# ABoatMon.net
KiCad netlist of a schematic drawn in EAGLE
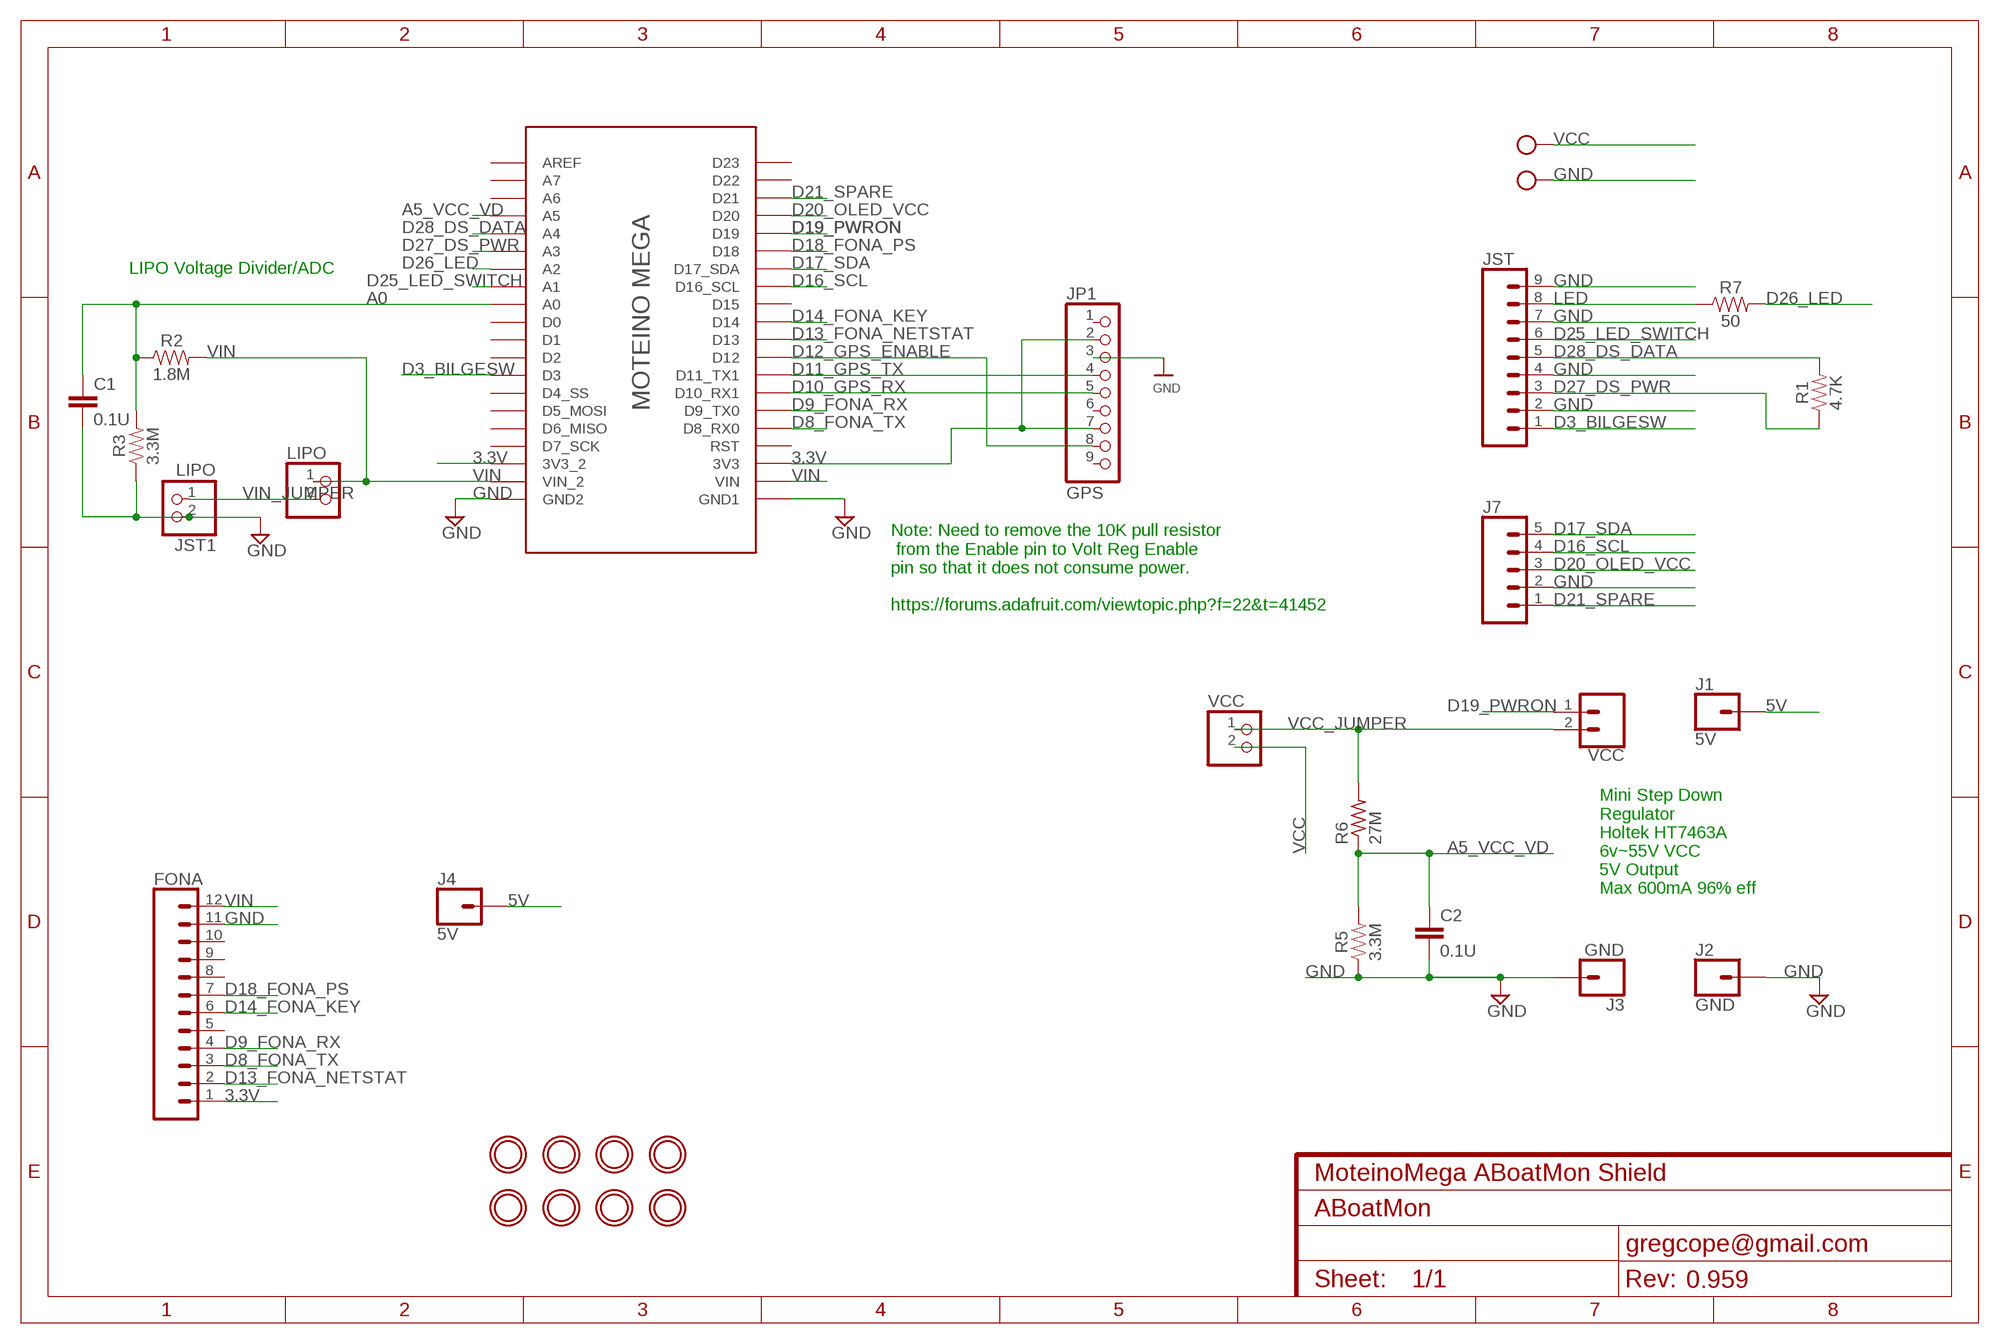
[diagram p0: schematic, sheet 1]

(export (version "E")
  (design (tool "Eeschema 10.0.6"))
  (components
    (comp (ref "C1")
      (value "0.1U")
      (footprint "eagle-import:CAP-PTH-SMALL-KIT")
      (libsource (lib "eagle-import") (part "0.1UF-KIT-EZ-50V-20%"))
    )
    (comp (ref "C2")
      (value "0.1U")
      (footprint "eagle-import:CAP-PTH-SMALL-KIT")
      (libsource (lib "eagle-import") (part "0.1UF-KIT-EZ-50V-20%"))
    )
    (comp (ref "ENABLE")
      (value "VCC")
      (footprint "eagle-import:1X02")
      (libsource (lib "eagle-import") (part "CONN_02"))
    )
    (comp (ref "FONA")
      (value "CONN_12")
      (footprint "eagle-import:1X12")
      (libsource (lib "eagle-import") (part "CONN_12"))
    )
    (comp (ref "GND")
      (value "MOUNTINGHOLE2.5")
      (footprint "eagle-import:MOUNTINGHOLE_2.5_PLATED")
      (libsource (lib "eagle-import") (part "MOUNTINGHOLE2.5"))
    )
    (comp (ref "J1")
      (value "5V")
      (footprint "eagle-import:1X01")
      (libsource (lib "eagle-import") (part "CONN_01"))
    )
    (comp (ref "J2")
      (value "GND")
      (footprint "eagle-import:1X01")
      (libsource (lib "eagle-import") (part "CONN_01"))
    )
    (comp (ref "J3")
      (value "GND")
      (footprint "eagle-import:1X01")
      (libsource (lib "eagle-import") (part "CONN_01"))
    )
    (comp (ref "J4")
      (value "5V")
      (footprint "eagle-import:1X01")
      (libsource (lib "eagle-import") (part "CONN_01"))
    )
    (comp (ref "J7")
      (value "CONN_05NO_SILK")
      (footprint "eagle-import:1X05_NO_SILK")
      (libsource (lib "eagle-import") (part "CONN_05NO_SILK"))
    )
    (comp (ref "JP1")
      (value "GPS")
      (footprint "eagle-import:1X09_ROUND_70")
      (libsource (lib "eagle-import") (part "HEADER-1X970MIL"))
    )
    (comp (ref "JST")
      (value "CONN_09")
      (footprint "eagle-import:1X09")
      (libsource (lib "eagle-import") (part "CONN_09"))
    )
    (comp (ref "JST1")
      (value "LIPO")
      (footprint "eagle-import:JST-PH-2-THM")
      (libsource (lib "eagle-import") (part "JST_2PIN-THM"))
    )
    (comp (ref "LIPO")
      (value "HEADER-1X2ROUND")
      (footprint "eagle-import:1X02_ROUND")
      (libsource (lib "eagle-import") (part "HEADER-1X2ROUND"))
    )
    (comp (ref "MOTEINO_MEGA")
      (value "HEADERS")
      (footprint "eagle-import:MOTEINO_MEGA_SIMPLE")
      (libsource (lib "eagle-import") (part "MOTEINO_MEGA_SIMPLE"))
    )
    (comp (ref "R1")
      (value "4.7K")
      (footprint "eagle-import:AXIAL-0.3")
      (libsource (lib "eagle-import") (part "1KOHM-HORIZ-1/4W-1%"))
    )
    (comp (ref "R2")
      (value "1.8M")
      (footprint "eagle-import:AXIAL-0.3")
      (libsource (lib "eagle-import") (part "1KOHM-HORIZ-1/4W-1%"))
    )
    (comp (ref "R3")
      (value "3.3M")
      (footprint "eagle-import:AXIAL-0.3")
      (libsource (lib "eagle-import") (part "1KOHM-HORIZ-1/4W-1%"))
    )
    (comp (ref "R5")
      (value "3.3M")
      (footprint "eagle-import:AXIAL-0.3")
      (libsource (lib "eagle-import") (part "1KOHM-HORIZ-1/4W-1%"))
    )
    (comp (ref "R6")
      (value "27M")
      (footprint "eagle-import:0309_12")
      (libsource (lib "eagle-import") (part "R-US_0309/12"))
    )
    (comp (ref "R7")
      (value "50")
      (footprint "eagle-import:AXIAL-0.3")
      (libsource (lib "eagle-import") (part "1KOHM-HORIZ-1/4W-1%"))
    )
    (comp (ref "U$1")
      (value "MOUNTINGHOLE2.5")
      (footprint "eagle-import:MOUNTINGHOLE_2.5_PLATED")
      (libsource (lib "eagle-import") (part "MOUNTINGHOLE2.5"))
    )
    (comp (ref "U$2")
      (value "MOUNTINGHOLE2.5")
      (footprint "eagle-import:MOUNTINGHOLE_2.5_PLATED")
      (libsource (lib "eagle-import") (part "MOUNTINGHOLE2.5"))
    )
    (comp (ref "U$3")
      (value "MOUNTINGHOLE2.5")
      (footprint "eagle-import:MOUNTINGHOLE_2.5_PLATED")
      (libsource (lib "eagle-import") (part "MOUNTINGHOLE2.5"))
    )
    (comp (ref "U$4")
      (value "MOUNTINGHOLE2.5")
      (footprint "eagle-import:MOUNTINGHOLE_2.5_PLATED")
      (libsource (lib "eagle-import") (part "MOUNTINGHOLE2.5"))
    )
    (comp (ref "U$5")
      (value "MOUNTINGHOLE2.5")
      (footprint "eagle-import:MOUNTINGHOLE_2.5_PLATED")
      (libsource (lib "eagle-import") (part "MOUNTINGHOLE2.5"))
    )
    (comp (ref "U$7")
      (value "MOUNTINGHOLE2.5")
      (footprint "eagle-import:MOUNTINGHOLE_2.5_PLATED")
      (libsource (lib "eagle-import") (part "MOUNTINGHOLE2.5"))
    )
    (comp (ref "U$8")
      (value "MOUNTINGHOLE2.5")
      (footprint "eagle-import:MOUNTINGHOLE_2.5_PLATED")
      (libsource (lib "eagle-import") (part "MOUNTINGHOLE2.5"))
    )
    (comp (ref "VCC")
      (value "HEADER-1X2ROUND")
      (footprint "eagle-import:1X02_ROUND")
      (libsource (lib "eagle-import") (part "HEADER-1X2ROUND"))
    )
    (comp (ref "X1")
      (value "MKDSN1,5/2-5,08")
      (footprint "eagle-import:MKDSN1,5_2-5,08")
      (libsource (lib "eagle-import") (part "MKDSN1,5/2-5,08"))
    )
  )
  (nets
    (net (code "1") (name "/3.3V") (class "Default")
      (node (ref "FONA") (pin "1") (pinfunction "1_1") (pintype "passive"))
      (node (ref "JP1") (pin "2") (pinfunction "2_2") (pintype "passive"))
      (node (ref "JP1") (pin "7") (pinfunction "7_7") (pintype "passive"))
      (node (ref "MOTEINO_MEGA") (pin "3V3") (pinfunction "3V3_3V3") (pintype "bidirectional"))
      (node (ref "MOTEINO_MEGA") (pin "3V3_2") (pinfunction "3V3_2_3V3_2") (pintype "bidirectional"))
    )
    (net (code "2") (name "/5V") (class "Default")
      (node (ref "J1") (pin "1") (pinfunction "1_1") (pintype "passive"))
      (node (ref "J4") (pin "1") (pinfunction "1_1") (pintype "passive"))
    )
    (net (code "3") (name "/A0") (class "Default")
      (node (ref "C1") (pin "1") (pinfunction "1_1") (pintype "passive"))
      (node (ref "MOTEINO_MEGA") (pin "A0") (pinfunction "A0_A0") (pintype "bidirectional"))
      (node (ref "R2") (pin "P$1") (pinfunction "1_P$1") (pintype "passive"))
      (node (ref "R3") (pin "P$2") (pinfunction "2_P$2") (pintype "passive"))
    )
    (net (code "4") (name "/A5_VCC_VD") (class "Default")
      (node (ref "C2") (pin "1") (pinfunction "1_1") (pintype "passive"))
      (node (ref "MOTEINO_MEGA") (pin "A5") (pinfunction "A5_A5") (pintype "bidirectional"))
      (node (ref "R5") (pin "P$2") (pinfunction "2_P$2") (pintype "passive"))
      (node (ref "R6") (pin "1") (pinfunction "1_1") (pintype "passive"))
    )
    (net (code "5") (name "/D3_BILGESW") (class "Default")
      (node (ref "JST") (pin "1") (pinfunction "1_1") (pintype "passive"))
      (node (ref "MOTEINO_MEGA") (pin "D3") (pinfunction "D3_D3") (pintype "bidirectional"))
    )
    (net (code "6") (name "/D8_FONA_TX") (class "Default")
      (node (ref "FONA") (pin "3") (pinfunction "3_3") (pintype "passive"))
      (node (ref "MOTEINO_MEGA") (pin "D8") (pinfunction "D8_RX0_D8") (pintype "bidirectional"))
    )
    (net (code "7") (name "/D9_FONA_RX") (class "Default")
      (node (ref "FONA") (pin "4") (pinfunction "4_4") (pintype "passive"))
      (node (ref "MOTEINO_MEGA") (pin "D9") (pinfunction "D9_TX0_D9") (pintype "bidirectional"))
    )
    (net (code "8") (name "/D10_GPS_RX") (class "Default")
      (node (ref "JP1") (pin "5") (pinfunction "5_5") (pintype "passive"))
      (node (ref "MOTEINO_MEGA") (pin "D10") (pinfunction "D10_RX1_D10") (pintype "bidirectional"))
    )
    (net (code "9") (name "/D11_GPS_TX") (class "Default")
      (node (ref "JP1") (pin "4") (pinfunction "4_4") (pintype "passive"))
      (node (ref "MOTEINO_MEGA") (pin "D11") (pinfunction "D11_TX1_D11") (pintype "bidirectional"))
    )
    (net (code "10") (name "/D12_GPS_ENABLE") (class "Default")
      (node (ref "JP1") (pin "8") (pinfunction "8_8") (pintype "passive"))
      (node (ref "MOTEINO_MEGA") (pin "D12") (pinfunction "D12_D12") (pintype "bidirectional"))
    )
    (net (code "11") (name "/D13_FONA_NETSTAT") (class "Default")
      (node (ref "FONA") (pin "2") (pinfunction "2_2") (pintype "passive"))
      (node (ref "MOTEINO_MEGA") (pin "D13") (pinfunction "D13_D13") (pintype "bidirectional"))
    )
    (net (code "12") (name "/D14_FONA_KEY") (class "Default")
      (node (ref "FONA") (pin "6") (pinfunction "6_6") (pintype "passive"))
      (node (ref "MOTEINO_MEGA") (pin "D14") (pinfunction "D14_D14") (pintype "bidirectional"))
    )
    (net (code "13") (name "/D16_SCL") (class "Default")
      (node (ref "J7") (pin "4") (pinfunction "4_4") (pintype "passive"))
      (node (ref "MOTEINO_MEGA") (pin "D16") (pinfunction "D16_SCL_D16") (pintype "bidirectional"))
    )
    (net (code "14") (name "/D17_SDA") (class "Default")
      (node (ref "J7") (pin "5") (pinfunction "5_5") (pintype "passive"))
      (node (ref "MOTEINO_MEGA") (pin "D17") (pinfunction "D17_SDA_D17") (pintype "bidirectional"))
    )
    (net (code "15") (name "/D18_FONA_PS") (class "Default")
      (node (ref "FONA") (pin "7") (pinfunction "7_7") (pintype "passive"))
      (node (ref "MOTEINO_MEGA") (pin "D18") (pinfunction "D18_D18") (pintype "bidirectional"))
    )
    (net (code "16") (name "/D19_PWRON") (class "Default")
      (node (ref "ENABLE") (pin "1") (pinfunction "1_1") (pintype "passive"))
      (node (ref "MOTEINO_MEGA") (pin "D19") (pinfunction "D19_D19") (pintype "bidirectional"))
    )
    (net (code "17") (name "/D20_OLED_VCC") (class "Default")
      (node (ref "J7") (pin "3") (pinfunction "3_3") (pintype "passive"))
      (node (ref "MOTEINO_MEGA") (pin "D20") (pinfunction "D20_D20") (pintype "bidirectional"))
    )
    (net (code "18") (name "/D21_SPARE") (class "Default")
      (node (ref "J7") (pin "1") (pinfunction "1_1") (pintype "passive"))
      (node (ref "MOTEINO_MEGA") (pin "D21") (pinfunction "D21_D21") (pintype "bidirectional"))
    )
    (net (code "19") (name "/D25_LED_SWITCH") (class "Default")
      (node (ref "JST") (pin "6") (pinfunction "6_6") (pintype "passive"))
      (node (ref "MOTEINO_MEGA") (pin "A1") (pinfunction "A1_A1") (pintype "bidirectional"))
    )
    (net (code "20") (name "/D26_LED") (class "Default")
      (node (ref "MOTEINO_MEGA") (pin "A2") (pinfunction "A2_A2") (pintype "bidirectional"))
      (node (ref "R7") (pin "P$2") (pinfunction "2_P$2") (pintype "passive"))
    )
    (net (code "21") (name "/D27_DS_PWR") (class "Default")
      (node (ref "JST") (pin "3") (pinfunction "3_3") (pintype "passive"))
      (node (ref "MOTEINO_MEGA") (pin "A3") (pinfunction "A3_A3") (pintype "bidirectional"))
      (node (ref "R1") (pin "P$1") (pinfunction "1_P$1") (pintype "passive"))
    )
    (net (code "22") (name "/D28_DS_DATA") (class "Default")
      (node (ref "JST") (pin "5") (pinfunction "5_5") (pintype "passive"))
      (node (ref "MOTEINO_MEGA") (pin "A4") (pinfunction "A4_A4") (pintype "bidirectional"))
      (node (ref "R1") (pin "P$2") (pinfunction "2_P$2") (pintype "passive"))
    )
    (net (code "23") (name "/LED") (class "Default")
      (node (ref "JST") (pin "8") (pinfunction "8_8") (pintype "passive"))
      (node (ref "R7") (pin "P$1") (pinfunction "1_P$1") (pintype "passive"))
    )
    (net (code "24") (name "/VCC") (class "Default")
      (node (ref "VCC") (pin "2") (pinfunction "2_2") (pintype "passive"))
      (node (ref "X1") (pin "1") (pinfunction "KL_1") (pintype "passive"))
    )
    (net (code "25") (name "/VCC_JUMPER") (class "Default")
      (node (ref "ENABLE") (pin "2") (pinfunction "2_2") (pintype "passive"))
      (node (ref "R6") (pin "2") (pinfunction "2_2") (pintype "passive"))
      (node (ref "VCC") (pin "1") (pinfunction "1_1") (pintype "passive"))
    )
    (net (code "26") (name "/VIN") (class "Default")
      (node (ref "FONA") (pin "12") (pinfunction "12_12") (pintype "passive"))
      (node (ref "LIPO") (pin "1") (pinfunction "1_1") (pintype "passive"))
      (node (ref "MOTEINO_MEGA") (pin "VIN") (pinfunction "VIN_VIN") (pintype "bidirectional"))
      (node (ref "MOTEINO_MEGA") (pin "VIN_2") (pinfunction "VIN_2_VIN_2") (pintype "bidirectional"))
      (node (ref "R2") (pin "P$2") (pinfunction "2_P$2") (pintype "passive"))
    )
    (net (code "27") (name "/VIN_JUMPER") (class "Default")
      (node (ref "JST1") (pin "1") (pinfunction "2_1") (pintype "passive"))
      (node (ref "LIPO") (pin "2") (pinfunction "2_2") (pintype "passive"))
    )
    (net (code "28") (name "GND") (class "Default")
      (node (ref "C1") (pin "2") (pinfunction "2_2") (pintype "passive"))
      (node (ref "C2") (pin "2") (pinfunction "2_2") (pintype "passive"))
      (node (ref "FONA") (pin "11") (pinfunction "11_11") (pintype "passive"))
      (node (ref "J2") (pin "1") (pinfunction "1_1") (pintype "passive"))
      (node (ref "J3") (pin "1") (pinfunction "1_1") (pintype "passive"))
      (node (ref "J7") (pin "2") (pinfunction "2_2") (pintype "passive"))
      (node (ref "JP1") (pin "3") (pinfunction "3_3") (pintype "passive"))
      (node (ref "JST") (pin "2") (pinfunction "2_2") (pintype "passive"))
      (node (ref "JST") (pin "4") (pinfunction "4_4") (pintype "passive"))
      (node (ref "JST") (pin "7") (pinfunction "7_7") (pintype "passive"))
      (node (ref "JST") (pin "9") (pinfunction "9_9") (pintype "passive"))
      (node (ref "JST1") (pin "2") (pinfunction "1_2") (pintype "passive"))
      (node (ref "MOTEINO_MEGA") (pin "GND1") (pinfunction "GND1_GND1") (pintype "bidirectional"))
      (node (ref "MOTEINO_MEGA") (pin "GND_2") (pinfunction "GND2_GND_2") (pintype "bidirectional"))
      (node (ref "R3") (pin "P$1") (pinfunction "1_P$1") (pintype "passive"))
      (node (ref "R5") (pin "P$1") (pinfunction "1_P$1") (pintype "passive"))
      (node (ref "X1") (pin "2") (pinfunction "KL_2") (pintype "passive"))
    )
    (net (code "29") (name "unconnected-(FONA-Pad5)") (class "Default")
      (node (ref "FONA") (pin "5") (pinfunction "5_5") (pintype "passive"))
    )
    (net (code "30") (name "unconnected-(FONA-Pad8)") (class "Default")
      (node (ref "FONA") (pin "8") (pinfunction "8_8") (pintype "passive"))
    )
    (net (code "31") (name "unconnected-(FONA-Pad9)") (class "Default")
      (node (ref "FONA") (pin "9") (pinfunction "9_9") (pintype "passive"))
    )
    (net (code "32") (name "unconnected-(FONA-Pad10)") (class "Default")
      (node (ref "FONA") (pin "10") (pinfunction "10_10") (pintype "passive"))
    )
    (net (code "33") (name "unconnected-(JP1-Pad1)") (class "Default")
      (node (ref "JP1") (pin "1") (pinfunction "1_1") (pintype "passive"))
    )
    (net (code "34") (name "unconnected-(JP1-Pad6)") (class "Default")
      (node (ref "JP1") (pin "6") (pinfunction "6_6") (pintype "passive"))
    )
    (net (code "35") (name "unconnected-(JP1-Pad9)") (class "Default")
      (node (ref "JP1") (pin "9") (pinfunction "9_9") (pintype "passive"))
    )
    (net (code "36") (name "unconnected-(MOTEINO_MEGA-D4_SS-PadD4)") (class "Default")
      (node (ref "MOTEINO_MEGA") (pin "D4") (pinfunction "D4_SS_D4") (pintype "bidirectional"))
    )
    (net (code "37") (name "unconnected-(MOTEINO_MEGA-D5_MOSI-PadD5)") (class "Default")
      (node (ref "MOTEINO_MEGA") (pin "D5") (pinfunction "D5_MOSI_D5") (pintype "bidirectional"))
    )
    (net (code "38") (name "unconnected-(MOTEINO_MEGA-D6_MISO-PadD6)") (class "Default")
      (node (ref "MOTEINO_MEGA") (pin "D6") (pinfunction "D6_MISO_D6") (pintype "bidirectional"))
    )
    (net (code "39") (name "unconnected-(MOTEINO_MEGA-D7_SCK-PadD7)") (class "Default")
      (node (ref "MOTEINO_MEGA") (pin "D7") (pinfunction "D7_SCK_D7") (pintype "bidirectional"))
    )
    (net (code "40") (name "unconnected-(MOTEINO_MEGA-PadA6)") (class "Default")
      (node (ref "MOTEINO_MEGA") (pin "A6") (pinfunction "A6_A6") (pintype "bidirectional"))
    )
    (net (code "41") (name "unconnected-(MOTEINO_MEGA-PadA7)") (class "Default")
      (node (ref "MOTEINO_MEGA") (pin "A7") (pinfunction "A7_A7") (pintype "bidirectional"))
    )
    (net (code "42") (name "unconnected-(MOTEINO_MEGA-PadAREF)") (class "Default")
      (node (ref "MOTEINO_MEGA") (pin "AREF") (pinfunction "AREF_AREF") (pintype "bidirectional"))
    )
    (net (code "43") (name "unconnected-(MOTEINO_MEGA-PadD0)") (class "Default")
      (node (ref "MOTEINO_MEGA") (pin "D0") (pinfunction "D0_D0") (pintype "bidirectional"))
    )
    (net (code "44") (name "unconnected-(MOTEINO_MEGA-PadD1)") (class "Default")
      (node (ref "MOTEINO_MEGA") (pin "D1") (pinfunction "D1_D1") (pintype "bidirectional"))
    )
    (net (code "45") (name "unconnected-(MOTEINO_MEGA-PadD2)") (class "Default")
      (node (ref "MOTEINO_MEGA") (pin "D2") (pinfunction "D2_D2") (pintype "bidirectional"))
    )
    (net (code "46") (name "unconnected-(MOTEINO_MEGA-PadD15)") (class "Default")
      (node (ref "MOTEINO_MEGA") (pin "D15") (pinfunction "D15_D15") (pintype "bidirectional"))
    )
    (net (code "47") (name "unconnected-(MOTEINO_MEGA-PadD22)") (class "Default")
      (node (ref "MOTEINO_MEGA") (pin "D22") (pinfunction "D22_D22") (pintype "bidirectional"))
    )
    (net (code "48") (name "unconnected-(MOTEINO_MEGA-PadD23)") (class "Default")
      (node (ref "MOTEINO_MEGA") (pin "D23") (pinfunction "D23_D23") (pintype "bidirectional"))
    )
    (net (code "49") (name "unconnected-(MOTEINO_MEGA-PadRST)") (class "Default")
      (node (ref "MOTEINO_MEGA") (pin "RST") (pinfunction "RST_RST") (pintype "bidirectional"))
    )
  )
)
